# SigCapture1.net
KiCad netlist of a schematic drawn in Altium Designer
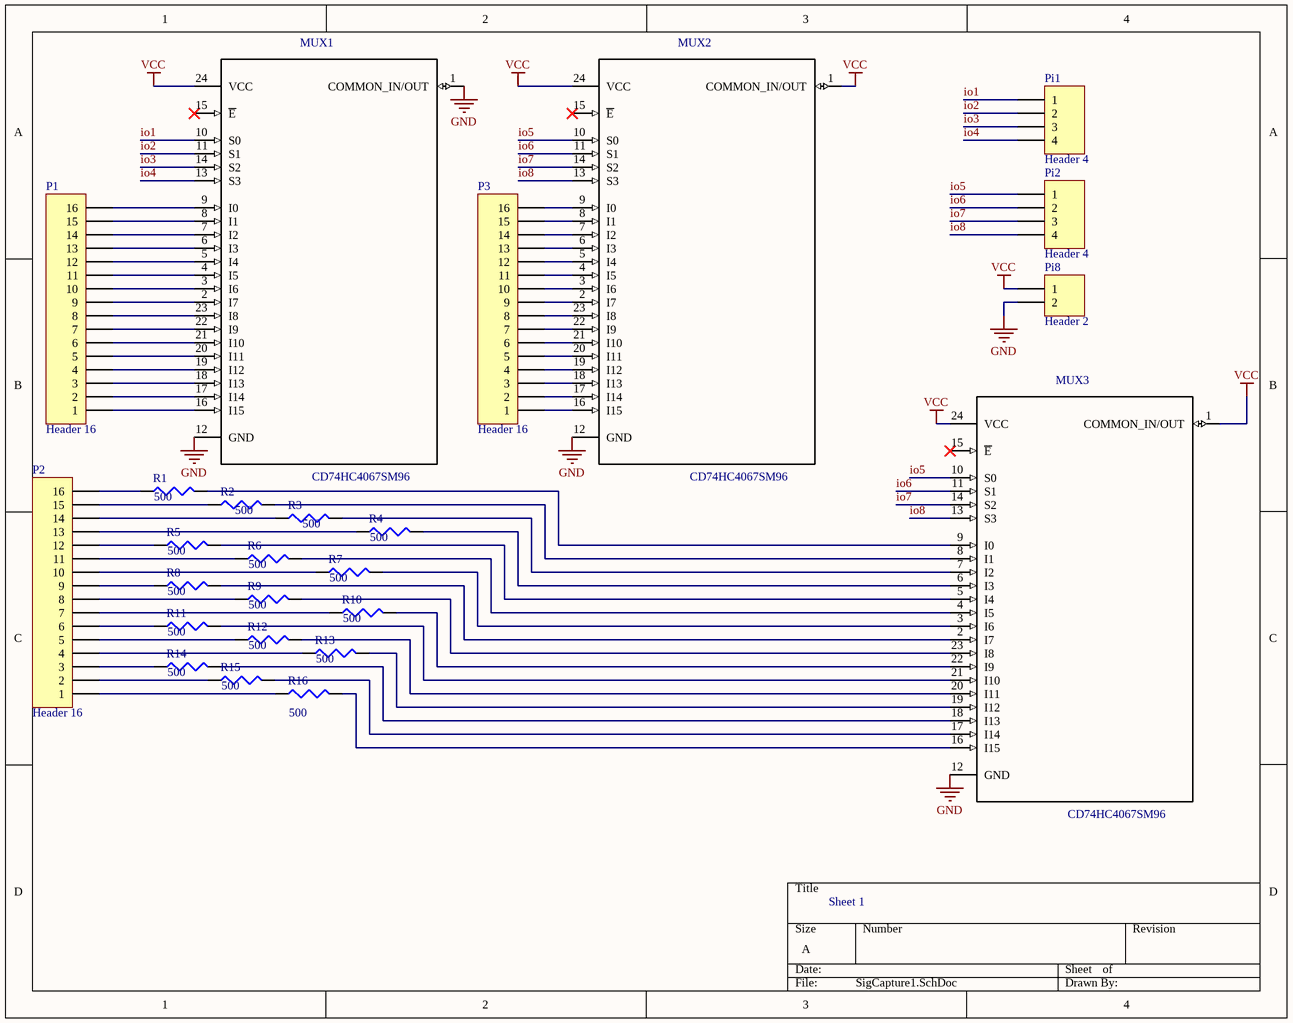
[diagram p0: SigCapture1.SchDoc]

(export (version "E")
  (design (tool "Eeschema 10.0.6"))
  (components
    (comp (ref "MUX1")
      (value "CD74HC4067SM96")
      (footprint "SOP65P780X200-24N")
      (description "High Speed CMOS 16-Channel Analog Multiplexer/Demultiplexer 24-SSOP -55 to 125")
      (fields (field (name "MF") "Texas Instruments"))
      (libsource (lib "CD74HC4067SM96") (part "CD74HC4067SM96"))
    )
    (comp (ref "MUX2")
      (value "CD74HC4067SM96")
      (footprint "SOP65P780X200-24N")
      (description "High Speed CMOS 16-Channel Analog Multiplexer/Demultiplexer 24-SSOP -55 to 125")
      (fields (field (name "MF") "Texas Instruments"))
      (libsource (lib "CD74HC4067SM96") (part "CD74HC4067SM96"))
    )
    (comp (ref "MUX3")
      (value "CD74HC4067SM96")
      (footprint "SOP65P780X200-24N")
      (description "High Speed CMOS 16-Channel Analog Multiplexer/Demultiplexer 24-SSOP -55 to 125")
      (fields (field (name "MF") "Texas Instruments"))
      (libsource (lib "CD74HC4067SM96") (part "CD74HC4067SM96"))
    )
    (comp (ref "P1")
      (value "Header 16")
      (footprint "HDR1X16")
      (description "Header, 16-Pin")
      (fields (field (name "PUBLISHER") "Altium Limited"))
      (libsource (lib "Miscellaneous Connectors") (part "Header 16"))
    )
    (comp (ref "P2")
      (value "Header 16")
      (footprint "HDR1X16")
      (description "Header, 16-Pin")
      (fields (field (name "PUBLISHER") "Altium Limited"))
      (libsource (lib "Miscellaneous Connectors") (part "Header 16"))
    )
    (comp (ref "P3")
      (value "Header 16")
      (footprint "HDR1X16")
      (description "Header, 16-Pin")
      (fields (field (name "PUBLISHER") "Altium Limited"))
      (libsource (lib "Miscellaneous Connectors") (part "Header 16"))
    )
    (comp (ref "Pi1")
      (value "Header 4")
      (footprint "HDR1X4")
      (description "Header, 4-Pin")
      (fields (field (name "PUBLISHER") "Altium Limited"))
      (libsource (lib "Miscellaneous Connectors") (part "Header 4"))
    )
    (comp (ref "Pi2")
      (value "Header 4")
      (footprint "HDR1X4")
      (description "Header, 4-Pin")
      (fields (field (name "PUBLISHER") "Altium Limited"))
      (libsource (lib "Miscellaneous Connectors") (part "Header 4"))
    )
    (comp (ref "Pi8")
      (value "Header 2")
      (footprint "HDR1X2")
      (description "Header, 2-Pin")
      (fields (field (name "PUBLISHER") "Altium Limited"))
      (libsource (lib "Miscellaneous Connectors") (part "Header 2"))
    )
    (comp (ref "R1")
      (value "500")
      (footprint "J1-0603")
      (description "Resistor")
      (fields (field (name "Comment") "Res3") (field (name "PUBLISHER") "Altium Limited"))
      (libsource (lib "Miscellaneous Devices") (part "Res3"))
    )
    (comp (ref "R2")
      (value "500")
      (footprint "J1-0603")
      (description "Resistor")
      (fields (field (name "Comment") "Res3") (field (name "PUBLISHER") "Altium Limited"))
      (libsource (lib "Miscellaneous Devices") (part "Res3"))
    )
    (comp (ref "R3")
      (value "500")
      (footprint "J1-0603")
      (description "Resistor")
      (fields (field (name "Comment") "Res3") (field (name "PUBLISHER") "Altium Limited"))
      (libsource (lib "Miscellaneous Devices") (part "Res3"))
    )
    (comp (ref "R4")
      (value "500")
      (footprint "J1-0603")
      (description "Resistor")
      (fields (field (name "Comment") "Res3") (field (name "PUBLISHER") "Altium Limited"))
      (libsource (lib "Miscellaneous Devices") (part "Res3"))
    )
    (comp (ref "R5")
      (value "500")
      (footprint "J1-0603")
      (description "Resistor")
      (fields (field (name "Comment") "Res3") (field (name "PUBLISHER") "Altium Limited"))
      (libsource (lib "Miscellaneous Devices") (part "Res3"))
    )
    (comp (ref "R6")
      (value "500")
      (footprint "J1-0603")
      (description "Resistor")
      (fields (field (name "Comment") "Res3") (field (name "PUBLISHER") "Altium Limited"))
      (libsource (lib "Miscellaneous Devices") (part "Res3"))
    )
    (comp (ref "R7")
      (value "500")
      (footprint "J1-0603")
      (description "Resistor")
      (fields (field (name "Comment") "Res3") (field (name "PUBLISHER") "Altium Limited"))
      (libsource (lib "Miscellaneous Devices") (part "Res3"))
    )
    (comp (ref "R8")
      (value "500")
      (footprint "J1-0603")
      (description "Resistor")
      (fields (field (name "Comment") "Res3") (field (name "PUBLISHER") "Altium Limited"))
      (libsource (lib "Miscellaneous Devices") (part "Res3"))
    )
    (comp (ref "R9")
      (value "500")
      (footprint "J1-0603")
      (description "Resistor")
      (fields (field (name "Comment") "Res3") (field (name "PUBLISHER") "Altium Limited"))
      (libsource (lib "Miscellaneous Devices") (part "Res3"))
    )
    (comp (ref "R10")
      (value "500")
      (footprint "J1-0603")
      (description "Resistor")
      (fields (field (name "Comment") "Res3") (field (name "PUBLISHER") "Altium Limited"))
      (libsource (lib "Miscellaneous Devices") (part "Res3"))
    )
    (comp (ref "R11")
      (value "500")
      (footprint "J1-0603")
      (description "Resistor")
      (fields (field (name "Comment") "Res3") (field (name "PUBLISHER") "Altium Limited"))
      (libsource (lib "Miscellaneous Devices") (part "Res3"))
    )
    (comp (ref "R12")
      (value "500")
      (footprint "J1-0603")
      (description "Resistor")
      (fields (field (name "Comment") "Res3") (field (name "PUBLISHER") "Altium Limited"))
      (libsource (lib "Miscellaneous Devices") (part "Res3"))
    )
    (comp (ref "R13")
      (value "500")
      (footprint "J1-0603")
      (description "Resistor")
      (fields (field (name "Comment") "Res3") (field (name "PUBLISHER") "Altium Limited"))
      (libsource (lib "Miscellaneous Devices") (part "Res3"))
    )
    (comp (ref "R14")
      (value "500")
      (footprint "J1-0603")
      (description "Resistor")
      (fields (field (name "Comment") "Res3") (field (name "PUBLISHER") "Altium Limited"))
      (libsource (lib "Miscellaneous Devices") (part "Res3"))
    )
    (comp (ref "R15")
      (value "500")
      (footprint "J1-0603")
      (description "Resistor")
      (fields (field (name "Comment") "Res3") (field (name "PUBLISHER") "Altium Limited"))
      (libsource (lib "Miscellaneous Devices") (part "Res3"))
    )
    (comp (ref "R16")
      (value "500")
      (footprint "J1-0603")
      (description "Resistor")
      (fields (field (name "Comment") "Res3") (field (name "PUBLISHER") "Altium Limited"))
      (libsource (lib "Miscellaneous Devices") (part "Res3"))
    )
  )
  (nets
    (net (code "1") (name "/io1") (class "Default")
      (node (ref "MUX1") (pin "10") (pinfunction "S0_10") (pintype "input"))
      (node (ref "Pi1") (pin "1") (pinfunction "1_1") (pintype "passive"))
    )
    (net (code "2") (name "/io2") (class "Default")
      (node (ref "MUX1") (pin "11") (pinfunction "S1_11") (pintype "input"))
      (node (ref "Pi1") (pin "2") (pinfunction "2_2") (pintype "passive"))
    )
    (net (code "3") (name "/io3") (class "Default")
      (node (ref "MUX1") (pin "14") (pinfunction "S2_14") (pintype "input"))
      (node (ref "Pi1") (pin "3") (pinfunction "3_3") (pintype "passive"))
    )
    (net (code "4") (name "/io4") (class "Default")
      (node (ref "MUX1") (pin "13") (pinfunction "S3_13") (pintype "input"))
      (node (ref "Pi1") (pin "4") (pinfunction "4_4") (pintype "passive"))
    )
    (net (code "5") (name "/io5") (class "Default")
      (node (ref "MUX2") (pin "10") (pinfunction "S0_10") (pintype "input"))
      (node (ref "MUX3") (pin "10") (pinfunction "S0_10") (pintype "input"))
      (node (ref "Pi2") (pin "1") (pinfunction "1_1") (pintype "passive"))
    )
    (net (code "6") (name "/io6") (class "Default")
      (node (ref "MUX2") (pin "11") (pinfunction "S1_11") (pintype "input"))
      (node (ref "MUX3") (pin "11") (pinfunction "S1_11") (pintype "input"))
      (node (ref "Pi2") (pin "2") (pinfunction "2_2") (pintype "passive"))
    )
    (net (code "7") (name "/io7") (class "Default")
      (node (ref "MUX2") (pin "14") (pinfunction "S2_14") (pintype "input"))
      (node (ref "MUX3") (pin "14") (pinfunction "S2_14") (pintype "input"))
      (node (ref "Pi2") (pin "3") (pinfunction "3_3") (pintype "passive"))
    )
    (net (code "8") (name "/io8") (class "Default")
      (node (ref "MUX2") (pin "13") (pinfunction "S3_13") (pintype "input"))
      (node (ref "MUX3") (pin "13") (pinfunction "S3_13") (pintype "input"))
      (node (ref "Pi2") (pin "4") (pinfunction "4_4") (pintype "passive"))
    )
    (net (code "9") (name "GND") (class "Default")
      (node (ref "MUX1") (pin "1") (pinfunction "COMMON_IN/OUT_1") (pintype "bidirectional"))
      (node (ref "MUX1") (pin "12") (pinfunction "GND_12") (pintype "passive"))
      (node (ref "MUX2") (pin "12") (pinfunction "GND_12") (pintype "passive"))
      (node (ref "MUX3") (pin "12") (pinfunction "GND_12") (pintype "passive"))
      (node (ref "Pi8") (pin "2") (pinfunction "2_2") (pintype "passive"))
    )
    (net (code "10") (name "Net-(MUX1-I0)") (class "Default")
      (node (ref "MUX1") (pin "9") (pinfunction "I0_9") (pintype "input"))
      (node (ref "P1") (pin "16") (pinfunction "16_16") (pintype "passive"))
    )
    (net (code "11") (name "Net-(MUX1-I1)") (class "Default")
      (node (ref "MUX1") (pin "8") (pinfunction "I1_8") (pintype "input"))
      (node (ref "P1") (pin "15") (pinfunction "15_15") (pintype "passive"))
    )
    (net (code "12") (name "Net-(MUX1-I2)") (class "Default")
      (node (ref "MUX1") (pin "7") (pinfunction "I2_7") (pintype "input"))
      (node (ref "P1") (pin "14") (pinfunction "14_14") (pintype "passive"))
    )
    (net (code "13") (name "Net-(MUX1-I3)") (class "Default")
      (node (ref "MUX1") (pin "6") (pinfunction "I3_6") (pintype "input"))
      (node (ref "P1") (pin "13") (pinfunction "13_13") (pintype "passive"))
    )
    (net (code "14") (name "Net-(MUX1-I4)") (class "Default")
      (node (ref "MUX1") (pin "5") (pinfunction "I4_5") (pintype "input"))
      (node (ref "P1") (pin "12") (pinfunction "12_12") (pintype "passive"))
    )
    (net (code "15") (name "Net-(MUX1-I5)") (class "Default")
      (node (ref "MUX1") (pin "4") (pinfunction "I5_4") (pintype "input"))
      (node (ref "P1") (pin "11") (pinfunction "11_11") (pintype "passive"))
    )
    (net (code "16") (name "Net-(MUX1-I6)") (class "Default")
      (node (ref "MUX1") (pin "3") (pinfunction "I6_3") (pintype "input"))
      (node (ref "P1") (pin "10") (pinfunction "10_10") (pintype "passive"))
    )
    (net (code "17") (name "Net-(MUX1-I7)") (class "Default")
      (node (ref "MUX1") (pin "2") (pinfunction "I7_2") (pintype "input"))
      (node (ref "P1") (pin "9") (pinfunction "9_9") (pintype "passive"))
    )
    (net (code "18") (name "Net-(MUX1-I8)") (class "Default")
      (node (ref "MUX1") (pin "23") (pinfunction "I8_23") (pintype "input"))
      (node (ref "P1") (pin "8") (pinfunction "8_8") (pintype "passive"))
    )
    (net (code "19") (name "Net-(MUX1-I9)") (class "Default")
      (node (ref "MUX1") (pin "22") (pinfunction "I9_22") (pintype "input"))
      (node (ref "P1") (pin "7") (pinfunction "7_7") (pintype "passive"))
    )
    (net (code "20") (name "Net-(MUX1-I10)") (class "Default")
      (node (ref "MUX1") (pin "21") (pinfunction "I10_21") (pintype "input"))
      (node (ref "P1") (pin "6") (pinfunction "6_6") (pintype "passive"))
    )
    (net (code "21") (name "Net-(MUX1-I11)") (class "Default")
      (node (ref "MUX1") (pin "20") (pinfunction "I11_20") (pintype "input"))
      (node (ref "P1") (pin "5") (pinfunction "5_5") (pintype "passive"))
    )
    (net (code "22") (name "Net-(MUX1-I12)") (class "Default")
      (node (ref "MUX1") (pin "19") (pinfunction "I12_19") (pintype "input"))
      (node (ref "P1") (pin "4") (pinfunction "4_4") (pintype "passive"))
    )
    (net (code "23") (name "Net-(MUX1-I13)") (class "Default")
      (node (ref "MUX1") (pin "18") (pinfunction "I13_18") (pintype "input"))
      (node (ref "P1") (pin "3") (pinfunction "3_3") (pintype "passive"))
    )
    (net (code "24") (name "Net-(MUX1-I14)") (class "Default")
      (node (ref "MUX1") (pin "17") (pinfunction "I14_17") (pintype "input"))
      (node (ref "P1") (pin "2") (pinfunction "2_2") (pintype "passive"))
    )
    (net (code "25") (name "Net-(MUX1-I15)") (class "Default")
      (node (ref "MUX1") (pin "16") (pinfunction "I15_16") (pintype "input"))
      (node (ref "P1") (pin "1") (pinfunction "1_1") (pintype "passive"))
    )
    (net (code "26") (name "Net-(MUX2-I0)") (class "Default")
      (node (ref "MUX2") (pin "9") (pinfunction "I0_9") (pintype "input"))
      (node (ref "P3") (pin "16") (pinfunction "16_16") (pintype "passive"))
    )
    (net (code "27") (name "Net-(MUX2-I1)") (class "Default")
      (node (ref "MUX2") (pin "8") (pinfunction "I1_8") (pintype "input"))
      (node (ref "P3") (pin "15") (pinfunction "15_15") (pintype "passive"))
    )
    (net (code "28") (name "Net-(MUX2-I2)") (class "Default")
      (node (ref "MUX2") (pin "7") (pinfunction "I2_7") (pintype "input"))
      (node (ref "P3") (pin "14") (pinfunction "14_14") (pintype "passive"))
    )
    (net (code "29") (name "Net-(MUX2-I3)") (class "Default")
      (node (ref "MUX2") (pin "6") (pinfunction "I3_6") (pintype "input"))
      (node (ref "P3") (pin "13") (pinfunction "13_13") (pintype "passive"))
    )
    (net (code "30") (name "Net-(MUX2-I4)") (class "Default")
      (node (ref "MUX2") (pin "5") (pinfunction "I4_5") (pintype "input"))
      (node (ref "P3") (pin "12") (pinfunction "12_12") (pintype "passive"))
    )
    (net (code "31") (name "Net-(MUX2-I5)") (class "Default")
      (node (ref "MUX2") (pin "4") (pinfunction "I5_4") (pintype "input"))
      (node (ref "P3") (pin "11") (pinfunction "11_11") (pintype "passive"))
    )
    (net (code "32") (name "Net-(MUX2-I6)") (class "Default")
      (node (ref "MUX2") (pin "3") (pinfunction "I6_3") (pintype "input"))
      (node (ref "P3") (pin "10") (pinfunction "10_10") (pintype "passive"))
    )
    (net (code "33") (name "Net-(MUX2-I7)") (class "Default")
      (node (ref "MUX2") (pin "2") (pinfunction "I7_2") (pintype "input"))
      (node (ref "P3") (pin "9") (pinfunction "9_9") (pintype "passive"))
    )
    (net (code "34") (name "Net-(MUX2-I8)") (class "Default")
      (node (ref "MUX2") (pin "23") (pinfunction "I8_23") (pintype "input"))
      (node (ref "P3") (pin "8") (pinfunction "8_8") (pintype "passive"))
    )
    (net (code "35") (name "Net-(MUX2-I9)") (class "Default")
      (node (ref "MUX2") (pin "22") (pinfunction "I9_22") (pintype "input"))
      (node (ref "P3") (pin "7") (pinfunction "7_7") (pintype "passive"))
    )
    (net (code "36") (name "Net-(MUX2-I10)") (class "Default")
      (node (ref "MUX2") (pin "21") (pinfunction "I10_21") (pintype "input"))
      (node (ref "P3") (pin "6") (pinfunction "6_6") (pintype "passive"))
    )
    (net (code "37") (name "Net-(MUX2-I11)") (class "Default")
      (node (ref "MUX2") (pin "20") (pinfunction "I11_20") (pintype "input"))
      (node (ref "P3") (pin "5") (pinfunction "5_5") (pintype "passive"))
    )
    (net (code "38") (name "Net-(MUX2-I12)") (class "Default")
      (node (ref "MUX2") (pin "19") (pinfunction "I12_19") (pintype "input"))
      (node (ref "P3") (pin "4") (pinfunction "4_4") (pintype "passive"))
    )
    (net (code "39") (name "Net-(MUX2-I13)") (class "Default")
      (node (ref "MUX2") (pin "18") (pinfunction "I13_18") (pintype "input"))
      (node (ref "P3") (pin "3") (pinfunction "3_3") (pintype "passive"))
    )
    (net (code "40") (name "Net-(MUX2-I14)") (class "Default")
      (node (ref "MUX2") (pin "17") (pinfunction "I14_17") (pintype "input"))
      (node (ref "P3") (pin "2") (pinfunction "2_2") (pintype "passive"))
    )
    (net (code "41") (name "Net-(MUX2-I15)") (class "Default")
      (node (ref "MUX2") (pin "16") (pinfunction "I15_16") (pintype "input"))
      (node (ref "P3") (pin "1") (pinfunction "1_1") (pintype "passive"))
    )
    (net (code "42") (name "Net-(MUX3-I0)") (class "Default")
      (node (ref "MUX3") (pin "9") (pinfunction "I0_9") (pintype "input"))
      (node (ref "R1") (pin "2") (pinfunction "2_2") (pintype "passive"))
    )
    (net (code "43") (name "Net-(MUX3-I1)") (class "Default")
      (node (ref "MUX3") (pin "8") (pinfunction "I1_8") (pintype "input"))
      (node (ref "R2") (pin "2") (pinfunction "2_2") (pintype "passive"))
    )
    (net (code "44") (name "Net-(MUX3-I2)") (class "Default")
      (node (ref "MUX3") (pin "7") (pinfunction "I2_7") (pintype "input"))
      (node (ref "R3") (pin "2") (pinfunction "2_2") (pintype "passive"))
    )
    (net (code "45") (name "Net-(MUX3-I3)") (class "Default")
      (node (ref "MUX3") (pin "6") (pinfunction "I3_6") (pintype "input"))
      (node (ref "R4") (pin "2") (pinfunction "2_2") (pintype "passive"))
    )
    (net (code "46") (name "Net-(MUX3-I4)") (class "Default")
      (node (ref "MUX3") (pin "5") (pinfunction "I4_5") (pintype "input"))
      (node (ref "R5") (pin "2") (pinfunction "2_2") (pintype "passive"))
    )
    (net (code "47") (name "Net-(MUX3-I5)") (class "Default")
      (node (ref "MUX3") (pin "4") (pinfunction "I5_4") (pintype "input"))
      (node (ref "R6") (pin "2") (pinfunction "2_2") (pintype "passive"))
    )
    (net (code "48") (name "Net-(MUX3-I6)") (class "Default")
      (node (ref "MUX3") (pin "3") (pinfunction "I6_3") (pintype "input"))
      (node (ref "R7") (pin "2") (pinfunction "2_2") (pintype "passive"))
    )
    (net (code "49") (name "Net-(MUX3-I7)") (class "Default")
      (node (ref "MUX3") (pin "2") (pinfunction "I7_2") (pintype "input"))
      (node (ref "R8") (pin "2") (pinfunction "2_2") (pintype "passive"))
    )
    (net (code "50") (name "Net-(MUX3-I8)") (class "Default")
      (node (ref "MUX3") (pin "23") (pinfunction "I8_23") (pintype "input"))
      (node (ref "R9") (pin "2") (pinfunction "2_2") (pintype "passive"))
    )
    (net (code "51") (name "Net-(MUX3-I9)") (class "Default")
      (node (ref "MUX3") (pin "22") (pinfunction "I9_22") (pintype "input"))
      (node (ref "R10") (pin "2") (pinfunction "2_2") (pintype "passive"))
    )
    (net (code "52") (name "Net-(MUX3-I10)") (class "Default")
      (node (ref "MUX3") (pin "21") (pinfunction "I10_21") (pintype "input"))
      (node (ref "R11") (pin "2") (pinfunction "2_2") (pintype "passive"))
    )
    (net (code "53") (name "Net-(MUX3-I11)") (class "Default")
      (node (ref "MUX3") (pin "20") (pinfunction "I11_20") (pintype "input"))
      (node (ref "R12") (pin "2") (pinfunction "2_2") (pintype "passive"))
    )
    (net (code "54") (name "Net-(MUX3-I12)") (class "Default")
      (node (ref "MUX3") (pin "19") (pinfunction "I12_19") (pintype "input"))
      (node (ref "R13") (pin "2") (pinfunction "2_2") (pintype "passive"))
    )
    (net (code "55") (name "Net-(MUX3-I13)") (class "Default")
      (node (ref "MUX3") (pin "18") (pinfunction "I13_18") (pintype "input"))
      (node (ref "R14") (pin "2") (pinfunction "2_2") (pintype "passive"))
    )
    (net (code "56") (name "Net-(MUX3-I14)") (class "Default")
      (node (ref "MUX3") (pin "17") (pinfunction "I14_17") (pintype "input"))
      (node (ref "R15") (pin "2") (pinfunction "2_2") (pintype "passive"))
    )
    (net (code "57") (name "Net-(MUX3-I15)") (class "Default")
      (node (ref "MUX3") (pin "16") (pinfunction "I15_16") (pintype "input"))
      (node (ref "R16") (pin "2") (pinfunction "2_2") (pintype "passive"))
    )
    (net (code "58") (name "Net-(P2-Pad1)") (class "Default")
      (node (ref "P2") (pin "1") (pinfunction "1_1") (pintype "passive"))
      (node (ref "R16") (pin "1") (pinfunction "1_1") (pintype "passive"))
    )
    (net (code "59") (name "Net-(P2-Pad2)") (class "Default")
      (node (ref "P2") (pin "2") (pinfunction "2_2") (pintype "passive"))
      (node (ref "R15") (pin "1") (pinfunction "1_1") (pintype "passive"))
    )
    (net (code "60") (name "Net-(P2-Pad3)") (class "Default")
      (node (ref "P2") (pin "3") (pinfunction "3_3") (pintype "passive"))
      (node (ref "R14") (pin "1") (pinfunction "1_1") (pintype "passive"))
    )
    (net (code "61") (name "Net-(P2-Pad4)") (class "Default")
      (node (ref "P2") (pin "4") (pinfunction "4_4") (pintype "passive"))
      (node (ref "R13") (pin "1") (pinfunction "1_1") (pintype "passive"))
    )
    (net (code "62") (name "Net-(P2-Pad5)") (class "Default")
      (node (ref "P2") (pin "5") (pinfunction "5_5") (pintype "passive"))
      (node (ref "R12") (pin "1") (pinfunction "1_1") (pintype "passive"))
    )
    (net (code "63") (name "Net-(P2-Pad6)") (class "Default")
      (node (ref "P2") (pin "6") (pinfunction "6_6") (pintype "passive"))
      (node (ref "R11") (pin "1") (pinfunction "1_1") (pintype "passive"))
    )
    (net (code "64") (name "Net-(P2-Pad7)") (class "Default")
      (node (ref "P2") (pin "7") (pinfunction "7_7") (pintype "passive"))
      (node (ref "R10") (pin "1") (pinfunction "1_1") (pintype "passive"))
    )
    (net (code "65") (name "Net-(P2-Pad8)") (class "Default")
      (node (ref "P2") (pin "8") (pinfunction "8_8") (pintype "passive"))
      (node (ref "R9") (pin "1") (pinfunction "1_1") (pintype "passive"))
    )
    (net (code "66") (name "Net-(P2-Pad9)") (class "Default")
      (node (ref "P2") (pin "9") (pinfunction "9_9") (pintype "passive"))
      (node (ref "R8") (pin "1") (pinfunction "1_1") (pintype "passive"))
    )
    (net (code "67") (name "Net-(P2-Pad10)") (class "Default")
      (node (ref "P2") (pin "10") (pinfunction "10_10") (pintype "passive"))
      (node (ref "R7") (pin "1") (pinfunction "1_1") (pintype "passive"))
    )
    (net (code "68") (name "Net-(P2-Pad11)") (class "Default")
      (node (ref "P2") (pin "11") (pinfunction "11_11") (pintype "passive"))
      (node (ref "R6") (pin "1") (pinfunction "1_1") (pintype "passive"))
    )
    (net (code "69") (name "Net-(P2-Pad12)") (class "Default")
      (node (ref "P2") (pin "12") (pinfunction "12_12") (pintype "passive"))
      (node (ref "R5") (pin "1") (pinfunction "1_1") (pintype "passive"))
    )
    (net (code "70") (name "Net-(P2-Pad13)") (class "Default")
      (node (ref "P2") (pin "13") (pinfunction "13_13") (pintype "passive"))
      (node (ref "R4") (pin "1") (pinfunction "1_1") (pintype "passive"))
    )
    (net (code "71") (name "Net-(P2-Pad14)") (class "Default")
      (node (ref "P2") (pin "14") (pinfunction "14_14") (pintype "passive"))
      (node (ref "R3") (pin "1") (pinfunction "1_1") (pintype "passive"))
    )
    (net (code "72") (name "Net-(P2-Pad15)") (class "Default")
      (node (ref "P2") (pin "15") (pinfunction "15_15") (pintype "passive"))
      (node (ref "R2") (pin "1") (pinfunction "1_1") (pintype "passive"))
    )
    (net (code "73") (name "Net-(P2-Pad16)") (class "Default")
      (node (ref "P2") (pin "16") (pinfunction "16_16") (pintype "passive"))
      (node (ref "R1") (pin "1") (pinfunction "1_1") (pintype "passive"))
    )
    (net (code "74") (name "VCC") (class "Default")
      (node (ref "MUX1") (pin "24") (pinfunction "VCC_24") (pintype "power_in"))
      (node (ref "MUX2") (pin "1") (pinfunction "COMMON_IN/OUT_1") (pintype "bidirectional"))
      (node (ref "MUX2") (pin "24") (pinfunction "VCC_24") (pintype "power_in"))
      (node (ref "MUX3") (pin "1") (pinfunction "COMMON_IN/OUT_1") (pintype "bidirectional"))
      (node (ref "MUX3") (pin "24") (pinfunction "VCC_24") (pintype "power_in"))
      (node (ref "Pi8") (pin "1") (pinfunction "1_1") (pintype "passive"))
    )
    (net (code "75") (name "unconnected-(MUX1-~{E}-Pad15)") (class "Default")
      (node (ref "MUX1") (pin "15") (pinfunction "~{E}_15") (pintype "input+no_connect"))
    )
    (net (code "76") (name "unconnected-(MUX2-~{E}-Pad15)") (class "Default")
      (node (ref "MUX2") (pin "15") (pinfunction "~{E}_15") (pintype "input+no_connect"))
    )
    (net (code "77") (name "unconnected-(MUX3-~{E}-Pad15)") (class "Default")
      (node (ref "MUX3") (pin "15") (pinfunction "~{E}_15") (pintype "input+no_connect"))
    )
  )
)
